# USB.net
KiCad netlist of a schematic drawn in Altium Designer
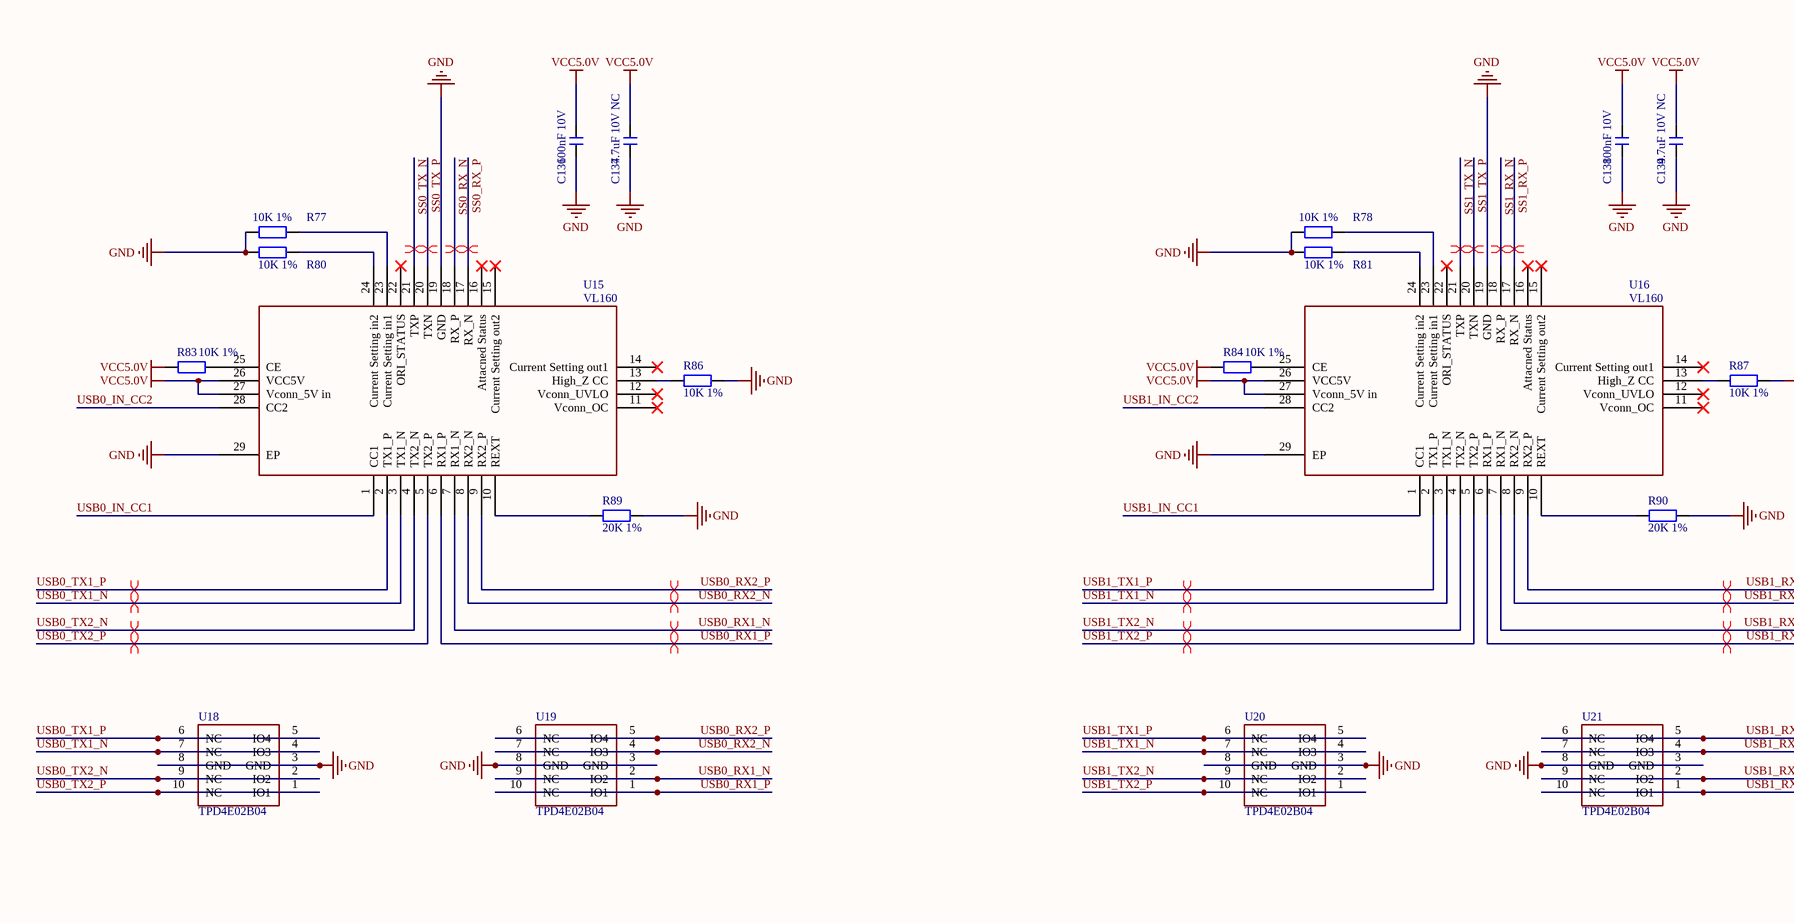
[diagram p0: USB.SchDoc, left]
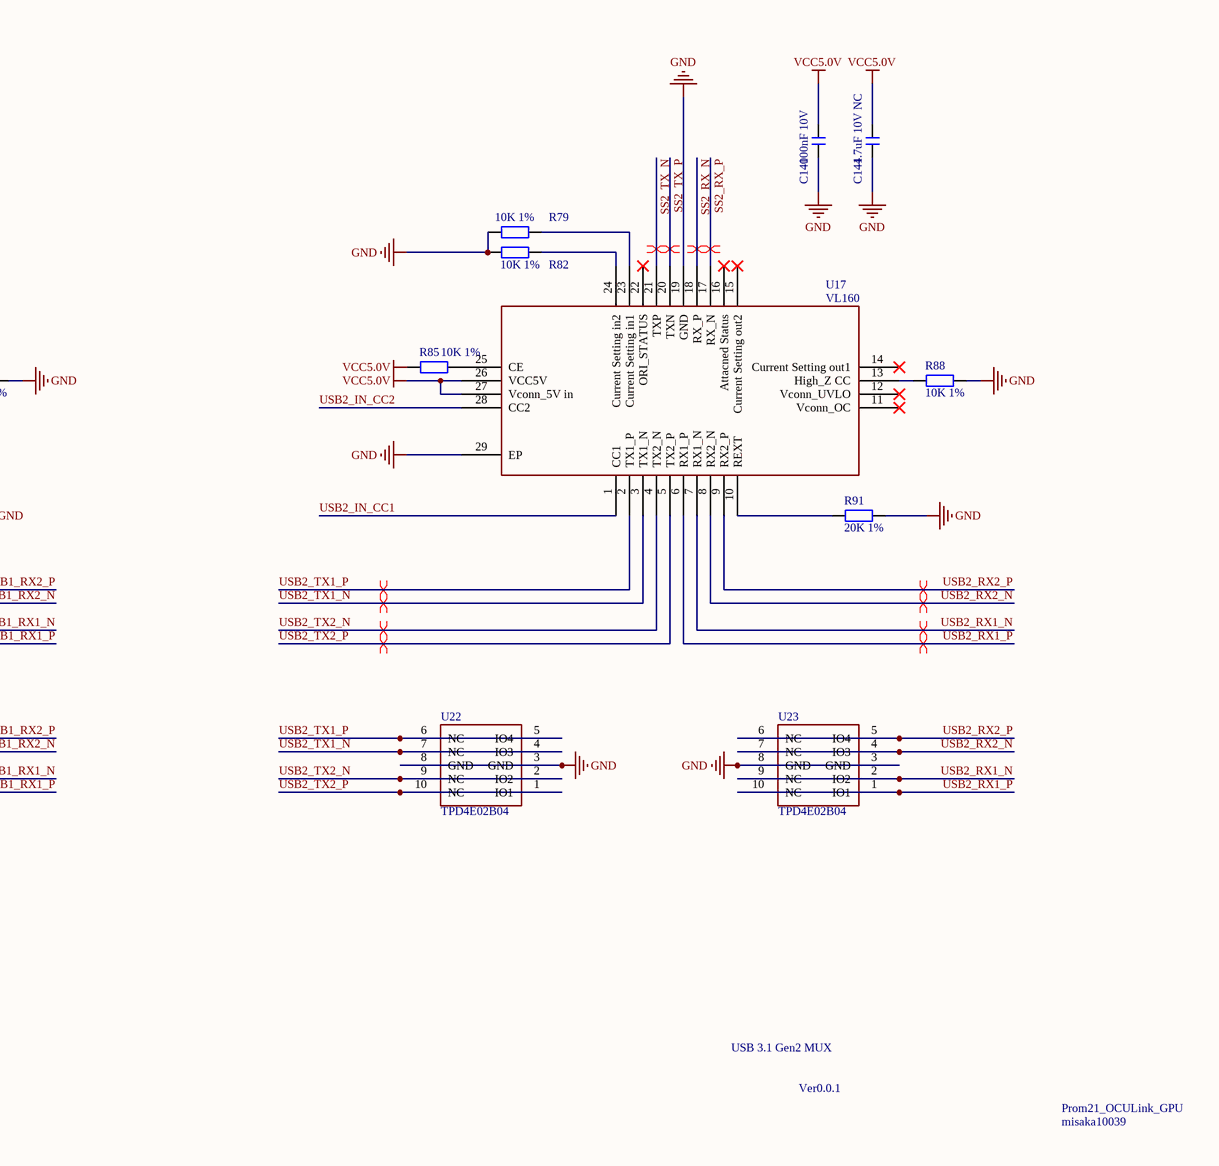
[diagram p1: USB.SchDoc, right]

(export (version "E")
  (design (tool "Eeschema 10.0.6"))
  (components
    (comp (ref "C136")
      (value "100nF 10V")
      (footprint "C0402_L")
      (description "无极性贴片电容")
      (fields (field (name "版权归属") "源创客"))
      (libsource (lib "Capacitor") (part "C"))
    )
    (comp (ref "C137")
      (value "4.7uF 10V NC")
      (footprint "C0402_L")
      (description "无极性贴片电容")
      (fields (field (name "版权归属") "源创客"))
      (libsource (lib "Capacitor") (part "C"))
    )
    (comp (ref "C138")
      (value "100nF 10V")
      (footprint "C0402_L")
      (description "无极性贴片电容")
      (fields (field (name "版权归属") "源创客"))
      (libsource (lib "Capacitor") (part "C"))
    )
    (comp (ref "C139")
      (value "4.7uF 10V NC")
      (footprint "C0402_L")
      (description "无极性贴片电容")
      (fields (field (name "版权归属") "源创客"))
      (libsource (lib "Capacitor") (part "C"))
    )
    (comp (ref "C140")
      (value "100nF 10V")
      (footprint "C0402_L")
      (description "无极性贴片电容")
      (fields (field (name "版权归属") "源创客"))
      (libsource (lib "Capacitor") (part "C"))
    )
    (comp (ref "C141")
      (value "4.7uF 10V NC")
      (footprint "C0402_L")
      (description "无极性贴片电容")
      (fields (field (name "版权归属") "源创客"))
      (libsource (lib "Capacitor") (part "C"))
    )
    (comp (ref "R77")
      (value "10K 1%")
      (footprint "R0402_L")
      (description "贴片电阻")
      (fields (field (name "版权归属") "源创客"))
      (libsource (lib "Resistor") (part "R"))
    )
    (comp (ref "R78")
      (value "10K 1%")
      (footprint "R0402_L")
      (description "贴片电阻")
      (fields (field (name "版权归属") "源创客"))
      (libsource (lib "Resistor") (part "R"))
    )
    (comp (ref "R79")
      (value "10K 1%")
      (footprint "R0402_L")
      (description "贴片电阻")
      (fields (field (name "版权归属") "源创客"))
      (libsource (lib "Resistor") (part "R"))
    )
    (comp (ref "R80")
      (value "10K 1%")
      (footprint "R0402_L")
      (description "贴片电阻")
      (fields (field (name "版权归属") "源创客"))
      (libsource (lib "Resistor") (part "R"))
    )
    (comp (ref "R81")
      (value "10K 1%")
      (footprint "R0402_L")
      (description "贴片电阻")
      (fields (field (name "版权归属") "源创客"))
      (libsource (lib "Resistor") (part "R"))
    )
    (comp (ref "R82")
      (value "10K 1%")
      (footprint "R0402_L")
      (description "贴片电阻")
      (fields (field (name "版权归属") "源创客"))
      (libsource (lib "Resistor") (part "R"))
    )
    (comp (ref "R83")
      (value "10K 1%")
      (footprint "R0402_L")
      (description "贴片电阻")
      (fields (field (name "版权归属") "源创客"))
      (libsource (lib "Resistor") (part "R"))
    )
    (comp (ref "R84")
      (value "10K 1%")
      (footprint "R0402_L")
      (description "贴片电阻")
      (fields (field (name "版权归属") "源创客"))
      (libsource (lib "Resistor") (part "R"))
    )
    (comp (ref "R85")
      (value "10K 1%")
      (footprint "R0402_L")
      (description "贴片电阻")
      (fields (field (name "版权归属") "源创客"))
      (libsource (lib "Resistor") (part "R"))
    )
    (comp (ref "R86")
      (value "10K 1%")
      (footprint "R0402_L")
      (description "贴片电阻")
      (fields (field (name "版权归属") "源创客"))
      (libsource (lib "Resistor") (part "R"))
    )
    (comp (ref "R87")
      (value "10K 1%")
      (footprint "R0402_L")
      (description "贴片电阻")
      (fields (field (name "版权归属") "源创客"))
      (libsource (lib "Resistor") (part "R"))
    )
    (comp (ref "R88")
      (value "10K 1%")
      (footprint "R0402_L")
      (description "贴片电阻")
      (fields (field (name "版权归属") "源创客"))
      (libsource (lib "Resistor") (part "R"))
    )
    (comp (ref "R89")
      (value "20K 1%")
      (footprint "R0402_L")
      (description "贴片电阻")
      (fields (field (name "版权归属") "源创客"))
      (libsource (lib "Resistor") (part "R"))
    )
    (comp (ref "R90")
      (value "20K 1%")
      (footprint "R0402_L")
      (description "贴片电阻")
      (fields (field (name "版权归属") "源创客"))
      (libsource (lib "Resistor") (part "R"))
    )
    (comp (ref "R91")
      (value "20K 1%")
      (footprint "R0402_L")
      (description "贴片电阻")
      (fields (field (name "版权归属") "源创客"))
      (libsource (lib "Resistor") (part "R"))
    )
    (comp (ref "U15")
      (value "VL160")
      (footprint "MQFN-28_L4.5-W3.5-P0.40-BL-EP")
      (libsource (lib "Brage") (part "VL160"))
    )
    (comp (ref "U16")
      (value "VL160")
      (footprint "MQFN-28_L4.5-W3.5-P0.40-BL-EP")
      (libsource (lib "Brage") (part "VL160"))
    )
    (comp (ref "U17")
      (value "VL160")
      (footprint "MQFN-28_L4.5-W3.5-P0.40-BL-EP")
      (libsource (lib "Brage") (part "VL160"))
    )
    (comp (ref "U18")
      (value "TPD4E02B04")
      (footprint "DIO_TPD4E02B04DQAR")
      (description "ESD")
      (libsource (lib "Diode") (part "TPD4E02B04"))
    )
    (comp (ref "U19")
      (value "TPD4E02B04")
      (footprint "DIO_TPD4E02B04DQAR")
      (description "ESD")
      (libsource (lib "Diode") (part "TPD4E02B04"))
    )
    (comp (ref "U20")
      (value "TPD4E02B04")
      (footprint "DIO_TPD4E02B04DQAR")
      (description "ESD")
      (libsource (lib "Diode") (part "TPD4E02B04"))
    )
    (comp (ref "U21")
      (value "TPD4E02B04")
      (footprint "DIO_TPD4E02B04DQAR")
      (description "ESD")
      (libsource (lib "Diode") (part "TPD4E02B04"))
    )
    (comp (ref "U22")
      (value "TPD4E02B04")
      (footprint "DIO_TPD4E02B04DQAR")
      (description "ESD")
      (libsource (lib "Diode") (part "TPD4E02B04"))
    )
    (comp (ref "U23")
      (value "TPD4E02B04")
      (footprint "DIO_TPD4E02B04DQAR")
      (description "ESD")
      (libsource (lib "Diode") (part "TPD4E02B04"))
    )
  )
  (nets
    (net (code "1") (name "/SS0_RX_N") (class "Default")
      (node (ref "U15") (pin "18") (pinfunction "RX_P_18") (pintype "passive"))
    )
    (net (code "2") (name "/SS0_RX_P") (class "Default")
      (node (ref "U15") (pin "17") (pinfunction "RX_N_17") (pintype "passive"))
    )
    (net (code "3") (name "/SS0_TX_N") (class "Default")
      (node (ref "U15") (pin "21") (pinfunction "TXP_21") (pintype "passive"))
    )
    (net (code "4") (name "/SS0_TX_P") (class "Default")
      (node (ref "U15") (pin "20") (pinfunction "TXN_20") (pintype "passive"))
    )
    (net (code "5") (name "/SS1_RX_N") (class "Default")
      (node (ref "U16") (pin "18") (pinfunction "RX_P_18") (pintype "passive"))
    )
    (net (code "6") (name "/SS1_RX_P") (class "Default")
      (node (ref "U16") (pin "17") (pinfunction "RX_N_17") (pintype "passive"))
    )
    (net (code "7") (name "/SS1_TX_N") (class "Default")
      (node (ref "U16") (pin "21") (pinfunction "TXP_21") (pintype "passive"))
    )
    (net (code "8") (name "/SS1_TX_P") (class "Default")
      (node (ref "U16") (pin "20") (pinfunction "TXN_20") (pintype "passive"))
    )
    (net (code "9") (name "/SS2_RX_N") (class "Default")
      (node (ref "U17") (pin "18") (pinfunction "RX_P_18") (pintype "passive"))
    )
    (net (code "10") (name "/SS2_RX_P") (class "Default")
      (node (ref "U17") (pin "17") (pinfunction "RX_N_17") (pintype "passive"))
    )
    (net (code "11") (name "/SS2_TX_N") (class "Default")
      (node (ref "U17") (pin "21") (pinfunction "TXP_21") (pintype "passive"))
    )
    (net (code "12") (name "/SS2_TX_P") (class "Default")
      (node (ref "U17") (pin "20") (pinfunction "TXN_20") (pintype "passive"))
    )
    (net (code "13") (name "/USB0_IN_CC1") (class "Default")
      (node (ref "U15") (pin "1") (pinfunction "CC1_1") (pintype "passive"))
    )
    (net (code "14") (name "/USB0_IN_CC2") (class "Default")
      (node (ref "U15") (pin "28") (pinfunction "CC2_28") (pintype "passive"))
    )
    (net (code "15") (name "/USB0_RX1_N") (class "Default")
      (node (ref "U15") (pin "7") (pinfunction "RX1_N_7") (pintype "passive"))
      (node (ref "U19") (pin "2") (pinfunction "IO2_2") (pintype "passive"))
      (node (ref "U19") (pin "9") (pinfunction "NC_9") (pintype "passive"))
    )
    (net (code "16") (name "/USB0_RX1_P") (class "Default")
      (node (ref "U15") (pin "6") (pinfunction "RX1_P_6") (pintype "passive"))
      (node (ref "U19") (pin "1") (pinfunction "IO1_1") (pintype "passive"))
      (node (ref "U19") (pin "10") (pinfunction "NC_10") (pintype "passive"))
    )
    (net (code "17") (name "/USB0_RX2_N") (class "Default")
      (node (ref "U15") (pin "8") (pinfunction "RX2_N_8") (pintype "passive"))
      (node (ref "U19") (pin "4") (pinfunction "IO3_4") (pintype "passive"))
      (node (ref "U19") (pin "7") (pinfunction "NC_7") (pintype "passive"))
    )
    (net (code "18") (name "/USB0_RX2_P") (class "Default")
      (node (ref "U15") (pin "9") (pinfunction "RX2_P_9") (pintype "passive"))
      (node (ref "U19") (pin "5") (pinfunction "IO4_5") (pintype "passive"))
      (node (ref "U19") (pin "6") (pinfunction "NC_6") (pintype "passive"))
    )
    (net (code "19") (name "/USB0_TX1_N") (class "Default")
      (node (ref "U15") (pin "3") (pinfunction "TX1_N_3") (pintype "passive"))
      (node (ref "U18") (pin "4") (pinfunction "IO3_4") (pintype "passive"))
      (node (ref "U18") (pin "7") (pinfunction "NC_7") (pintype "passive"))
    )
    (net (code "20") (name "/USB0_TX1_P") (class "Default")
      (node (ref "U15") (pin "2") (pinfunction "TX1_P_2") (pintype "passive"))
      (node (ref "U18") (pin "5") (pinfunction "IO4_5") (pintype "passive"))
      (node (ref "U18") (pin "6") (pinfunction "NC_6") (pintype "passive"))
    )
    (net (code "21") (name "/USB0_TX2_N") (class "Default")
      (node (ref "U15") (pin "4") (pinfunction "TX2_N_4") (pintype "passive"))
      (node (ref "U18") (pin "2") (pinfunction "IO2_2") (pintype "passive"))
      (node (ref "U18") (pin "9") (pinfunction "NC_9") (pintype "passive"))
    )
    (net (code "22") (name "/USB0_TX2_P") (class "Default")
      (node (ref "U15") (pin "5") (pinfunction "TX2_P_5") (pintype "passive"))
      (node (ref "U18") (pin "1") (pinfunction "IO1_1") (pintype "passive"))
      (node (ref "U18") (pin "10") (pinfunction "NC_10") (pintype "passive"))
    )
    (net (code "23") (name "/USB1_IN_CC1") (class "Default")
      (node (ref "U16") (pin "1") (pinfunction "CC1_1") (pintype "passive"))
    )
    (net (code "24") (name "/USB1_IN_CC2") (class "Default")
      (node (ref "U16") (pin "28") (pinfunction "CC2_28") (pintype "passive"))
    )
    (net (code "25") (name "/USB1_RX1_N") (class "Default")
      (node (ref "U16") (pin "7") (pinfunction "RX1_N_7") (pintype "passive"))
      (node (ref "U21") (pin "2") (pinfunction "IO2_2") (pintype "passive"))
      (node (ref "U21") (pin "9") (pinfunction "NC_9") (pintype "passive"))
    )
    (net (code "26") (name "/USB1_RX1_P") (class "Default")
      (node (ref "U16") (pin "6") (pinfunction "RX1_P_6") (pintype "passive"))
      (node (ref "U21") (pin "1") (pinfunction "IO1_1") (pintype "passive"))
      (node (ref "U21") (pin "10") (pinfunction "NC_10") (pintype "passive"))
    )
    (net (code "27") (name "/USB1_RX2_N") (class "Default")
      (node (ref "U16") (pin "8") (pinfunction "RX2_N_8") (pintype "passive"))
      (node (ref "U21") (pin "4") (pinfunction "IO3_4") (pintype "passive"))
      (node (ref "U21") (pin "7") (pinfunction "NC_7") (pintype "passive"))
    )
    (net (code "28") (name "/USB1_RX2_P") (class "Default")
      (node (ref "U16") (pin "9") (pinfunction "RX2_P_9") (pintype "passive"))
      (node (ref "U21") (pin "5") (pinfunction "IO4_5") (pintype "passive"))
      (node (ref "U21") (pin "6") (pinfunction "NC_6") (pintype "passive"))
    )
    (net (code "29") (name "/USB1_TX1_N") (class "Default")
      (node (ref "U16") (pin "3") (pinfunction "TX1_N_3") (pintype "passive"))
      (node (ref "U20") (pin "4") (pinfunction "IO3_4") (pintype "passive"))
      (node (ref "U20") (pin "7") (pinfunction "NC_7") (pintype "passive"))
    )
    (net (code "30") (name "/USB1_TX1_P") (class "Default")
      (node (ref "U16") (pin "2") (pinfunction "TX1_P_2") (pintype "passive"))
      (node (ref "U20") (pin "5") (pinfunction "IO4_5") (pintype "passive"))
      (node (ref "U20") (pin "6") (pinfunction "NC_6") (pintype "passive"))
    )
    (net (code "31") (name "/USB1_TX2_N") (class "Default")
      (node (ref "U16") (pin "4") (pinfunction "TX2_N_4") (pintype "passive"))
      (node (ref "U20") (pin "2") (pinfunction "IO2_2") (pintype "passive"))
      (node (ref "U20") (pin "9") (pinfunction "NC_9") (pintype "passive"))
    )
    (net (code "32") (name "/USB1_TX2_P") (class "Default")
      (node (ref "U16") (pin "5") (pinfunction "TX2_P_5") (pintype "passive"))
      (node (ref "U20") (pin "1") (pinfunction "IO1_1") (pintype "passive"))
      (node (ref "U20") (pin "10") (pinfunction "NC_10") (pintype "passive"))
    )
    (net (code "33") (name "/USB2_IN_CC1") (class "Default")
      (node (ref "U17") (pin "1") (pinfunction "CC1_1") (pintype "passive"))
    )
    (net (code "34") (name "/USB2_IN_CC2") (class "Default")
      (node (ref "U17") (pin "28") (pinfunction "CC2_28") (pintype "passive"))
    )
    (net (code "35") (name "/USB2_RX1_N") (class "Default")
      (node (ref "U17") (pin "7") (pinfunction "RX1_N_7") (pintype "passive"))
      (node (ref "U23") (pin "2") (pinfunction "IO2_2") (pintype "passive"))
      (node (ref "U23") (pin "9") (pinfunction "NC_9") (pintype "passive"))
    )
    (net (code "36") (name "/USB2_RX1_P") (class "Default")
      (node (ref "U17") (pin "6") (pinfunction "RX1_P_6") (pintype "passive"))
      (node (ref "U23") (pin "1") (pinfunction "IO1_1") (pintype "passive"))
      (node (ref "U23") (pin "10") (pinfunction "NC_10") (pintype "passive"))
    )
    (net (code "37") (name "/USB2_RX2_N") (class "Default")
      (node (ref "U17") (pin "8") (pinfunction "RX2_N_8") (pintype "passive"))
      (node (ref "U23") (pin "4") (pinfunction "IO3_4") (pintype "passive"))
      (node (ref "U23") (pin "7") (pinfunction "NC_7") (pintype "passive"))
    )
    (net (code "38") (name "/USB2_RX2_P") (class "Default")
      (node (ref "U17") (pin "9") (pinfunction "RX2_P_9") (pintype "passive"))
      (node (ref "U23") (pin "5") (pinfunction "IO4_5") (pintype "passive"))
      (node (ref "U23") (pin "6") (pinfunction "NC_6") (pintype "passive"))
    )
    (net (code "39") (name "/USB2_TX1_N") (class "Default")
      (node (ref "U17") (pin "3") (pinfunction "TX1_N_3") (pintype "passive"))
      (node (ref "U22") (pin "4") (pinfunction "IO3_4") (pintype "passive"))
      (node (ref "U22") (pin "7") (pinfunction "NC_7") (pintype "passive"))
    )
    (net (code "40") (name "/USB2_TX1_P") (class "Default")
      (node (ref "U17") (pin "2") (pinfunction "TX1_P_2") (pintype "passive"))
      (node (ref "U22") (pin "5") (pinfunction "IO4_5") (pintype "passive"))
      (node (ref "U22") (pin "6") (pinfunction "NC_6") (pintype "passive"))
    )
    (net (code "41") (name "/USB2_TX2_N") (class "Default")
      (node (ref "U17") (pin "4") (pinfunction "TX2_N_4") (pintype "passive"))
      (node (ref "U22") (pin "2") (pinfunction "IO2_2") (pintype "passive"))
      (node (ref "U22") (pin "9") (pinfunction "NC_9") (pintype "passive"))
    )
    (net (code "42") (name "/USB2_TX2_P") (class "Default")
      (node (ref "U17") (pin "5") (pinfunction "TX2_P_5") (pintype "passive"))
      (node (ref "U22") (pin "1") (pinfunction "IO1_1") (pintype "passive"))
      (node (ref "U22") (pin "10") (pinfunction "NC_10") (pintype "passive"))
    )
    (net (code "43") (name "GND") (class "Default")
      (node (ref "C136") (pin "1") (pinfunction "1_1") (pintype "passive"))
      (node (ref "C137") (pin "1") (pinfunction "1_1") (pintype "passive"))
      (node (ref "C138") (pin "1") (pinfunction "1_1") (pintype "passive"))
      (node (ref "C139") (pin "1") (pinfunction "1_1") (pintype "passive"))
      (node (ref "C140") (pin "1") (pinfunction "1_1") (pintype "passive"))
      (node (ref "C141") (pin "1") (pinfunction "1_1") (pintype "passive"))
      (node (ref "R77") (pin "1") (pinfunction "1_1") (pintype "passive"))
      (node (ref "R78") (pin "1") (pinfunction "1_1") (pintype "passive"))
      (node (ref "R79") (pin "1") (pinfunction "1_1") (pintype "passive"))
      (node (ref "R80") (pin "1") (pinfunction "1_1") (pintype "passive"))
      (node (ref "R81") (pin "1") (pinfunction "1_1") (pintype "passive"))
      (node (ref "R82") (pin "1") (pinfunction "1_1") (pintype "passive"))
      (node (ref "R86") (pin "1") (pinfunction "1_1") (pintype "passive"))
      (node (ref "R87") (pin "1") (pinfunction "1_1") (pintype "passive"))
      (node (ref "R88") (pin "1") (pinfunction "1_1") (pintype "passive"))
      (node (ref "R89") (pin "1") (pinfunction "1_1") (pintype "passive"))
      (node (ref "R90") (pin "1") (pinfunction "1_1") (pintype "passive"))
      (node (ref "R91") (pin "1") (pinfunction "1_1") (pintype "passive"))
      (node (ref "U15") (pin "19") (pinfunction "GND_19") (pintype "passive"))
      (node (ref "U15") (pin "29") (pinfunction "EP_29") (pintype "passive"))
      (node (ref "U16") (pin "19") (pinfunction "GND_19") (pintype "passive"))
      (node (ref "U16") (pin "29") (pinfunction "EP_29") (pintype "passive"))
      (node (ref "U17") (pin "19") (pinfunction "GND_19") (pintype "passive"))
      (node (ref "U17") (pin "29") (pinfunction "EP_29") (pintype "passive"))
      (node (ref "U18") (pin "3") (pinfunction "GND_3") (pintype "passive"))
      (node (ref "U18") (pin "8") (pinfunction "GND_8") (pintype "passive"))
      (node (ref "U19") (pin "3") (pinfunction "GND_3") (pintype "passive"))
      (node (ref "U19") (pin "8") (pinfunction "GND_8") (pintype "passive"))
      (node (ref "U20") (pin "3") (pinfunction "GND_3") (pintype "passive"))
      (node (ref "U20") (pin "8") (pinfunction "GND_8") (pintype "passive"))
      (node (ref "U21") (pin "3") (pinfunction "GND_3") (pintype "passive"))
      (node (ref "U21") (pin "8") (pinfunction "GND_8") (pintype "passive"))
      (node (ref "U22") (pin "3") (pinfunction "GND_3") (pintype "passive"))
      (node (ref "U22") (pin "8") (pinfunction "GND_8") (pintype "passive"))
      (node (ref "U23") (pin "3") (pinfunction "GND_3") (pintype "passive"))
      (node (ref "U23") (pin "8") (pinfunction "GND_8") (pintype "passive"))
    )
    (net (code "44") (name "Net-(U15-CE)") (class "Default")
      (node (ref "R83") (pin "1") (pinfunction "1_1") (pintype "passive"))
      (node (ref "U15") (pin "25") (pinfunction "CE_25") (pintype "passive"))
    )
    (net (code "45") (name "Net-(U15-Current_Setting_in1)") (class "Default")
      (node (ref "R77") (pin "2") (pinfunction "2_2") (pintype "passive"))
      (node (ref "U15") (pin "23") (pinfunction "Current_Setting_in1_23") (pintype "passive"))
    )
    (net (code "46") (name "Net-(U15-Current_Setting_in2)") (class "Default")
      (node (ref "R80") (pin "2") (pinfunction "2_2") (pintype "passive"))
      (node (ref "U15") (pin "24") (pinfunction "Current_Setting_in2_24") (pintype "passive"))
    )
    (net (code "47") (name "Net-(U15-High_Z_CC)") (class "Default")
      (node (ref "R86") (pin "2") (pinfunction "2_2") (pintype "passive"))
      (node (ref "U15") (pin "13") (pinfunction "High_Z_CC_13") (pintype "passive"))
    )
    (net (code "48") (name "Net-(U15-REXT)") (class "Default")
      (node (ref "R89") (pin "2") (pinfunction "2_2") (pintype "passive"))
      (node (ref "U15") (pin "10") (pinfunction "REXT_10") (pintype "passive"))
    )
    (net (code "49") (name "Net-(U16-CE)") (class "Default")
      (node (ref "R84") (pin "1") (pinfunction "1_1") (pintype "passive"))
      (node (ref "U16") (pin "25") (pinfunction "CE_25") (pintype "passive"))
    )
    (net (code "50") (name "Net-(U16-Current_Setting_in1)") (class "Default")
      (node (ref "R78") (pin "2") (pinfunction "2_2") (pintype "passive"))
      (node (ref "U16") (pin "23") (pinfunction "Current_Setting_in1_23") (pintype "passive"))
    )
    (net (code "51") (name "Net-(U16-Current_Setting_in2)") (class "Default")
      (node (ref "R81") (pin "2") (pinfunction "2_2") (pintype "passive"))
      (node (ref "U16") (pin "24") (pinfunction "Current_Setting_in2_24") (pintype "passive"))
    )
    (net (code "52") (name "Net-(U16-High_Z_CC)") (class "Default")
      (node (ref "R87") (pin "2") (pinfunction "2_2") (pintype "passive"))
      (node (ref "U16") (pin "13") (pinfunction "High_Z_CC_13") (pintype "passive"))
    )
    (net (code "53") (name "Net-(U16-REXT)") (class "Default")
      (node (ref "R90") (pin "2") (pinfunction "2_2") (pintype "passive"))
      (node (ref "U16") (pin "10") (pinfunction "REXT_10") (pintype "passive"))
    )
    (net (code "54") (name "Net-(U17-CE)") (class "Default")
      (node (ref "R85") (pin "1") (pinfunction "1_1") (pintype "passive"))
      (node (ref "U17") (pin "25") (pinfunction "CE_25") (pintype "passive"))
    )
    (net (code "55") (name "Net-(U17-Current_Setting_in1)") (class "Default")
      (node (ref "R79") (pin "2") (pinfunction "2_2") (pintype "passive"))
      (node (ref "U17") (pin "23") (pinfunction "Current_Setting_in1_23") (pintype "passive"))
    )
    (net (code "56") (name "Net-(U17-Current_Setting_in2)") (class "Default")
      (node (ref "R82") (pin "2") (pinfunction "2_2") (pintype "passive"))
      (node (ref "U17") (pin "24") (pinfunction "Current_Setting_in2_24") (pintype "passive"))
    )
    (net (code "57") (name "Net-(U17-High_Z_CC)") (class "Default")
      (node (ref "R88") (pin "2") (pinfunction "2_2") (pintype "passive"))
      (node (ref "U17") (pin "13") (pinfunction "High_Z_CC_13") (pintype "passive"))
    )
    (net (code "58") (name "Net-(U17-REXT)") (class "Default")
      (node (ref "R91") (pin "2") (pinfunction "2_2") (pintype "passive"))
      (node (ref "U17") (pin "10") (pinfunction "REXT_10") (pintype "passive"))
    )
    (net (code "59") (name "VCC5.0V") (class "Default")
      (node (ref "C136") (pin "2") (pinfunction "2_2") (pintype "passive"))
      (node (ref "C137") (pin "2") (pinfunction "2_2") (pintype "passive"))
      (node (ref "C138") (pin "2") (pinfunction "2_2") (pintype "passive"))
      (node (ref "C139") (pin "2") (pinfunction "2_2") (pintype "passive"))
      (node (ref "C140") (pin "2") (pinfunction "2_2") (pintype "passive"))
      (node (ref "C141") (pin "2") (pinfunction "2_2") (pintype "passive"))
      (node (ref "R83") (pin "2") (pinfunction "2_2") (pintype "passive"))
      (node (ref "R84") (pin "2") (pinfunction "2_2") (pintype "passive"))
      (node (ref "R85") (pin "2") (pinfunction "2_2") (pintype "passive"))
      (node (ref "U15") (pin "26") (pinfunction "VCC5V_26") (pintype "passive"))
      (node (ref "U15") (pin "27") (pinfunction "Vconn_5V_in_27") (pintype "passive"))
      (node (ref "U16") (pin "26") (pinfunction "VCC5V_26") (pintype "passive"))
      (node (ref "U16") (pin "27") (pinfunction "Vconn_5V_in_27") (pintype "passive"))
      (node (ref "U17") (pin "26") (pinfunction "VCC5V_26") (pintype "passive"))
      (node (ref "U17") (pin "27") (pinfunction "Vconn_5V_in_27") (pintype "passive"))
    )
    (net (code "60") (name "unconnected-(U15-Attacned_Status-Pad16)") (class "Default")
      (node (ref "U15") (pin "16") (pinfunction "Attacned_Status_16") (pintype "passive+no_connect"))
    )
    (net (code "61") (name "unconnected-(U15-Current_Setting_out1-Pad14)") (class "Default")
      (node (ref "U15") (pin "14") (pinfunction "Current_Setting_out1_14") (pintype "passive+no_connect"))
    )
    (net (code "62") (name "unconnected-(U15-Current_Setting_out2-Pad15)") (class "Default")
      (node (ref "U15") (pin "15") (pinfunction "Current_Setting_out2_15") (pintype "passive+no_connect"))
    )
    (net (code "63") (name "unconnected-(U15-ORI_STATUS-Pad22)") (class "Default")
      (node (ref "U15") (pin "22") (pinfunction "ORI_STATUS_22") (pintype "passive+no_connect"))
    )
    (net (code "64") (name "unconnected-(U15-Vconn_OC-Pad11)") (class "Default")
      (node (ref "U15") (pin "11") (pinfunction "Vconn_OC_11") (pintype "passive+no_connect"))
    )
    (net (code "65") (name "unconnected-(U15-Vconn_UVLO-Pad12)") (class "Default")
      (node (ref "U15") (pin "12") (pinfunction "Vconn_UVLO_12") (pintype "passive+no_connect"))
    )
    (net (code "66") (name "unconnected-(U16-Attacned_Status-Pad16)") (class "Default")
      (node (ref "U16") (pin "16") (pinfunction "Attacned_Status_16") (pintype "passive+no_connect"))
    )
    (net (code "67") (name "unconnected-(U16-Current_Setting_out1-Pad14)") (class "Default")
      (node (ref "U16") (pin "14") (pinfunction "Current_Setting_out1_14") (pintype "passive+no_connect"))
    )
    (net (code "68") (name "unconnected-(U16-Current_Setting_out2-Pad15)") (class "Default")
      (node (ref "U16") (pin "15") (pinfunction "Current_Setting_out2_15") (pintype "passive+no_connect"))
    )
    (net (code "69") (name "unconnected-(U16-ORI_STATUS-Pad22)") (class "Default")
      (node (ref "U16") (pin "22") (pinfunction "ORI_STATUS_22") (pintype "passive+no_connect"))
    )
    (net (code "70") (name "unconnected-(U16-Vconn_OC-Pad11)") (class "Default")
      (node (ref "U16") (pin "11") (pinfunction "Vconn_OC_11") (pintype "passive+no_connect"))
    )
    (net (code "71") (name "unconnected-(U16-Vconn_UVLO-Pad12)") (class "Default")
      (node (ref "U16") (pin "12") (pinfunction "Vconn_UVLO_12") (pintype "passive+no_connect"))
    )
    (net (code "72") (name "unconnected-(U17-Attacned_Status-Pad16)") (class "Default")
      (node (ref "U17") (pin "16") (pinfunction "Attacned_Status_16") (pintype "passive+no_connect"))
    )
    (net (code "73") (name "unconnected-(U17-Current_Setting_out1-Pad14)") (class "Default")
      (node (ref "U17") (pin "14") (pinfunction "Current_Setting_out1_14") (pintype "passive+no_connect"))
    )
    (net (code "74") (name "unconnected-(U17-Current_Setting_out2-Pad15)") (class "Default")
      (node (ref "U17") (pin "15") (pinfunction "Current_Setting_out2_15") (pintype "passive+no_connect"))
    )
    (net (code "75") (name "unconnected-(U17-ORI_STATUS-Pad22)") (class "Default")
      (node (ref "U17") (pin "22") (pinfunction "ORI_STATUS_22") (pintype "passive+no_connect"))
    )
    (net (code "76") (name "unconnected-(U17-Vconn_OC-Pad11)") (class "Default")
      (node (ref "U17") (pin "11") (pinfunction "Vconn_OC_11") (pintype "passive+no_connect"))
    )
    (net (code "77") (name "unconnected-(U17-Vconn_UVLO-Pad12)") (class "Default")
      (node (ref "U17") (pin "12") (pinfunction "Vconn_UVLO_12") (pintype "passive+no_connect"))
    )
  )
)
